# Eload_Aux_Supply_Module_Rev_2.net
KiCad netlist of a schematic drawn in Altium Designer
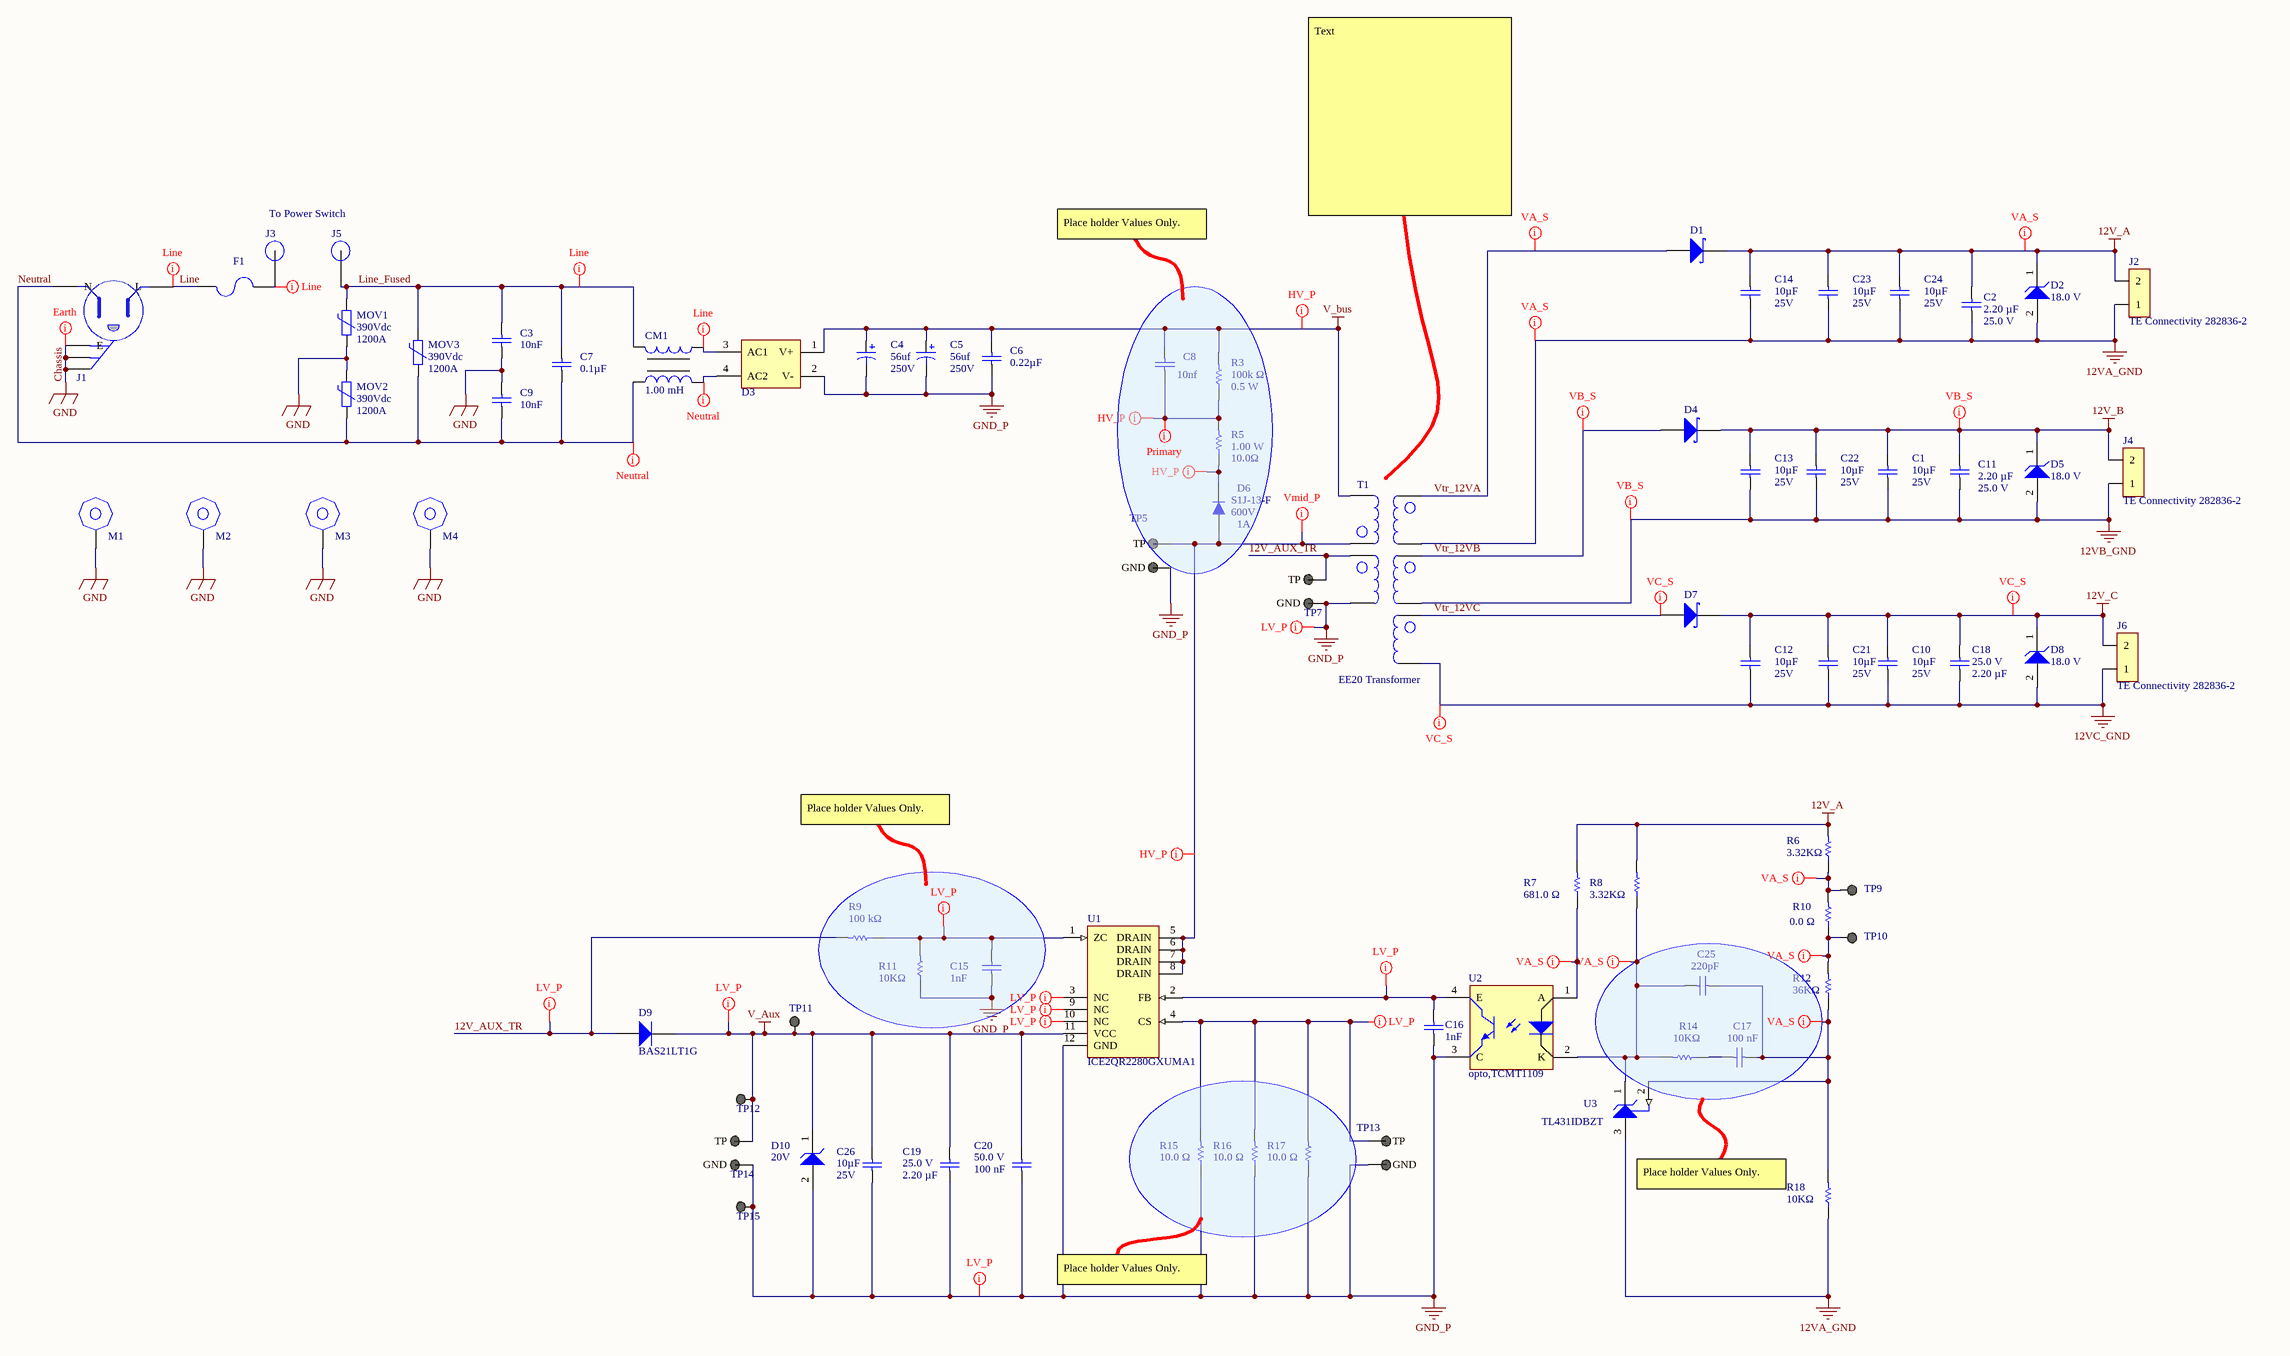
[diagram p0: Eload Aux Supply Module Rev 2.SchDoc]

(export (version "E")
  (design (tool "Eeschema 10.0.6"))
  (components
    (comp (ref "C1")
      (value "Cap")
      (footprint "Cap, 1206")
      (description "10µF ±10% 25V Ceramic Capacitor X7R 1206 (3216 Metric)")
      (fields
        (field (name "MANUFACTURER") "TDK Corporation")
        (field (name "TOLERANCE") "±10%")
        (field (name "CAPACITANCE") "10µF")
        (field (name "VOLTAGE - RATED") "25V")
      )
      (libsource (lib "Master Oct28_2018") (part "CAP,1206,10uF,25V,C3216X7R1E106K160AB"))
    )
    (comp (ref "C2")
      (value "AVX 08053C225KAT2A")
      (footprint "CAP, 0805, HD")
      (description "0805 2.2 uF 25 V ±10 % Tolerance X7R SMT Multilayer Ceramic Capacitor")
      (fields
        (field (name "MANUFACTURER PART NUMBER") "08053C225KAT2A")
        (field (name "VOLTAGE RATING (DC)") "25.0 V")
        (field (name "CAPACITANCE") "2.20 µF")
      )
      (libsource (lib "Master Oct28_2018") (part "Cap,0805,2.2uF,25V,±10%"))
    )
    (comp (ref "C3")
      (value "Cap")
      (footprint "Cap,7.5mm,RFI")
      (description "10000pF ±20% 300VAC Ceramic Capacitor F Radial, Disc")
      (fields
        (field (name "MANUFACTURER") "Murata Electronics North America")
        (field (name "CAPACITANCE") "10nF")
        (field (name "TOLERANCE") "±20%")
      )
      (libsource (lib "Master JUL_2019-Shawn") (part "Cap,RFI,TH,7.5mm,10nF,300Vac,10nF,DE2F3KY103MN3AU02F"))
    )
    (comp (ref "C4")
      (value "Cap,polar,through hole,12.5mm,56uf,250V,20%,UCY2E560MHD1TO")
      (footprint "Cap, Rad, 5mmLead,12.5mmDia,Pin 2+")
      (description "Cap Alum 56uf 20% 250v Radial")
      (fields
        (field (name "MANUFACTURER PART NUMBER") "UCY2E560MHD1TO")
        (field (name "CAP") "56uf")
        (field (name "VOLTAGE RATING") "250V")
      )
      (libsource (lib "Master Oct28_2018") (part "Cap,polar,through hole,12.5mm,56uf,250V,20%,UCY2E560MHD1TO"))
    )
    (comp (ref "C5")
      (value "Cap,polar,through hole,12.5mm,56uf,250V,20%,UCY2E560MHD1TO")
      (footprint "Cap, Rad, 5mmLead,12.5mmDia,Pin 2+")
      (description "Cap Alum 56uf 20% 250v Radial")
      (fields
        (field (name "MANUFACTURER PART NUMBER") "UCY2E560MHD1TO")
        (field (name "CAP") "56uf")
        (field (name "VOLTAGE RATING") "250V")
      )
      (libsource (lib "Master Oct28_2018") (part "Cap,polar,through hole,12.5mm,56uf,250V,20%,UCY2E560MHD1TO"))
    )
    (comp (ref "C6")
      (value "Cap")
      (footprint "Cap, 5mm Lead Spaceing, 4mm dai")
      (description "0.22µF ±10% 250V Ceramic Capacitor X7R Radial")
      (fields
        (field (name "MANUFACTURER") "TDK Corporation")
        (field (name "TOLERANCE") "±10%")
        (field (name "CAPACITANCE") "0.22µF")
      )
      (libsource (lib "Master Oct28_2018") (part "Cap,TH,General Putpose,5mm Spacing, 220nF,250V,FG20X7R2E224KNT06"))
    )
    (comp (ref "C7")
      (value "Cap")
      (footprint "CAP,RFI,15mm Lead Spaceing")
      (description "0.1µF Film Capacitor 305V 630V Polypropylene (PP) Radial")
      (fields
        (field (name "MANUFACTURER") "EPCOS (TDK)")
        (field (name "TOLERANCE") "±20%")
        (field (name "CAPACITANCE") "0.1µF")
      )
      (libsource (lib "Master JUL_2019-Shawn") (part "Cap,RFI,TH,15mm,100nF,305VAC,20%, B32922C3104M000"))
    )
    (comp (ref "C8")
      (value "10nf")
      (footprint "Cap, 5mm Lead Spaceing, 4mm dai")
      (description "10000pF ±5% 630V Ceramic Capacitor C0G, NP0 Radial")
      (fields (field (name "TOLERANCE") "±5%"))
      (libsource (lib "Master Oct28_2018") (part "Cap,,snubber, 10nf,5mm,spacing,630,FG26C0G2J103JNT06"))
    )
    (comp (ref "C9")
      (value "Cap")
      (footprint "Cap,7.5mm,RFI")
      (description "10000pF ±20% 300VAC Ceramic Capacitor F Radial, Disc")
      (fields
        (field (name "MANUFACTURER") "Murata Electronics North America")
        (field (name "CAPACITANCE") "10nF")
        (field (name "TOLERANCE") "±20%")
      )
      (libsource (lib "Master JUL_2019-Shawn") (part "Cap,RFI,TH,7.5mm,10nF,300Vac,10nF,DE2F3KY103MN3AU02F"))
    )
    (comp (ref "C10")
      (value "Cap")
      (footprint "Cap, 1206")
      (description "10µF ±10% 25V Ceramic Capacitor X7R 1206 (3216 Metric)")
      (fields
        (field (name "MANUFACTURER") "TDK Corporation")
        (field (name "TOLERANCE") "±10%")
        (field (name "CAPACITANCE") "10µF")
        (field (name "VOLTAGE - RATED") "25V")
      )
      (libsource (lib "Master Oct28_2018") (part "CAP,1206,10uF,25V,C3216X7R1E106K160AB"))
    )
    (comp (ref "C11")
      (value "AVX 08053C225KAT2A")
      (footprint "CAP, 0805, HD")
      (description "0805 2.2 uF 25 V ±10 % Tolerance X7R SMT Multilayer Ceramic Capacitor")
      (fields
        (field (name "MANUFACTURER PART NUMBER") "08053C225KAT2A")
        (field (name "VOLTAGE RATING (DC)") "25.0 V")
        (field (name "CAPACITANCE") "2.20 µF")
      )
      (libsource (lib "Master Oct28_2018") (part "Cap,0805,2.2uF,25V,±10%"))
    )
    (comp (ref "C12")
      (value "Cap")
      (footprint "Cap, 1206")
      (description "10µF ±10% 25V Ceramic Capacitor X7R 1206 (3216 Metric)")
      (fields
        (field (name "MANUFACTURER") "TDK Corporation")
        (field (name "TOLERANCE") "±10%")
        (field (name "CAPACITANCE") "10µF")
        (field (name "VOLTAGE - RATED") "25V")
      )
      (libsource (lib "Master Oct28_2018") (part "CAP,1206,10uF,25V,C3216X7R1E106K160AB"))
    )
    (comp (ref "C13")
      (value "Cap")
      (footprint "Cap, 1206")
      (description "10µF ±10% 25V Ceramic Capacitor X7R 1206 (3216 Metric)")
      (fields
        (field (name "MANUFACTURER") "TDK Corporation")
        (field (name "TOLERANCE") "±10%")
        (field (name "CAPACITANCE") "10µF")
        (field (name "VOLTAGE - RATED") "25V")
      )
      (libsource (lib "Master Oct28_2018") (part "CAP,1206,10uF,25V,C3216X7R1E106K160AB"))
    )
    (comp (ref "C14")
      (value "Cap")
      (footprint "Cap, 1206")
      (description "10µF ±10% 25V Ceramic Capacitor X7R 1206 (3216 Metric)")
      (fields
        (field (name "MANUFACTURER") "TDK Corporation")
        (field (name "TOLERANCE") "±10%")
        (field (name "CAPACITANCE") "10µF")
        (field (name "VOLTAGE - RATED") "25V")
      )
      (libsource (lib "Master Oct28_2018") (part "CAP,1206,10uF,25V,C3216X7R1E106K160AB"))
    )
    (comp (ref "C15")
      (value "Kemet C0805X102J1GACAUTO")
      (footprint "CAP, 0805, HD")
      (description "CAPACITOR, 1NF, 100V, NP0, 0805")
      (fields (field (name "CAPACITANCE") "1nF"))
      (libsource (lib "Master Oct28_2018") (part "Cap,0805n,1nF,±5%,100Vdc"))
    )
    (comp (ref "C16")
      (value "Kemet C0805X102J1GACAUTO")
      (footprint "CAP, 0805, HD")
      (description "CAPACITOR, 1NF, 100V, NP0, 0805")
      (fields (field (name "CAPACITANCE") "1nF"))
      (libsource (lib "Master Oct28_2018") (part "Cap,0805,1nF,±5%,100Vdc"))
    )
    (comp (ref "C17")
      (value "08055C104JAT2A")
      (footprint "CAP, 0805, HD")
      (description "Capacitor; Ceramic; Cap 0.1 uF; Tol 5%; Vol-Rtg 50 VDC; SMT; 0805; X7R; Tape & Reel")
      (fields (field (name "CAPACITANCE") "100 nF"))
      (libsource (lib "Master Oct28_2018") (part "Cap,0805,100nf,50V,5%,08055C104JAT2A"))
    )
    (comp (ref "C18")
      (value "AVX 08053C225KAT2A")
      (footprint "CAP, 0805, HD")
      (description "0805 2.2 uF 25 V ±10 % Tolerance X7R SMT Multilayer Ceramic Capacitor")
      (fields
        (field (name "MANUFACTURER PART NUMBER") "08053C225KAT2A")
        (field (name "VOLTAGE RATING (DC)") "25.0 V")
        (field (name "CAPACITANCE") "2.20 µF")
      )
      (libsource (lib "Master Oct28_2018") (part "Cap,0805,2.2uF,25V,±10%"))
    )
    (comp (ref "C19")
      (value "AVX 08053C225KAT2A")
      (footprint "CAP, 0805, HD")
      (description "0805 2.2 uF 25 V ±10 % Tolerance X7R SMT Multilayer Ceramic Capacitor")
      (fields
        (field (name "MANUFACTURER PART NUMBER") "08053C225KAT2A")
        (field (name "VOLTAGE RATING (DC)") "25.0 V")
        (field (name "CAPACITANCE") "2.20 µF")
      )
      (libsource (lib "Master Oct28_2018") (part "Cap,0805,2.2uF,25V,±10%"))
    )
    (comp (ref "C20")
      (value "08055C104JAT2A")
      (footprint "CAP, 0805, HD")
      (description "Capacitor; Ceramic; Cap 0.1 uF; Tol 5%; Vol-Rtg 50 VDC; SMT; 0805; X7R; Tape & Reel")
      (fields (field (name "VOLTAGE RATING (DC)") "50.0 V") (field (name "CAPACITANCE") "100 nF"))
      (libsource (lib "Master Oct28_2018") (part "Cap,0805,100nf,50V,5%,08055C104JAT2A"))
    )
    (comp (ref "C21")
      (value "Cap")
      (footprint "Cap, 1206")
      (description "10µF ±10% 25V Ceramic Capacitor X7R 1206 (3216 Metric)")
      (fields
        (field (name "MANUFACTURER") "TDK Corporation")
        (field (name "TOLERANCE") "±10%")
        (field (name "CAPACITANCE") "10µF")
        (field (name "VOLTAGE - RATED") "25V")
      )
      (libsource (lib "Master Oct28_2018") (part "CAP,1206,10uF,25V,C3216X7R1E106K160AB"))
    )
    (comp (ref "C22")
      (value "Cap")
      (footprint "Cap, 1206")
      (description "10µF ±10% 25V Ceramic Capacitor X7R 1206 (3216 Metric)")
      (fields
        (field (name "MANUFACTURER") "TDK Corporation")
        (field (name "TOLERANCE") "±10%")
        (field (name "CAPACITANCE") "10µF")
        (field (name "VOLTAGE - RATED") "25V")
      )
      (libsource (lib "Master Oct28_2018") (part "CAP,1206,10uF,25V,C3216X7R1E106K160AB"))
    )
    (comp (ref "C23")
      (value "Cap")
      (footprint "Cap, 1206")
      (description "10µF ±10% 25V Ceramic Capacitor X7R 1206 (3216 Metric)")
      (fields
        (field (name "MANUFACTURER") "TDK Corporation")
        (field (name "TOLERANCE") "±10%")
        (field (name "CAPACITANCE") "10µF")
        (field (name "VOLTAGE - RATED") "25V")
      )
      (libsource (lib "Master Oct28_2018") (part "CAP,1206,10uF,25V,C3216X7R1E106K160AB"))
    )
    (comp (ref "C24")
      (value "Cap")
      (footprint "Cap, 1206")
      (description "10µF ±10% 25V Ceramic Capacitor X7R 1206 (3216 Metric)")
      (fields
        (field (name "MANUFACTURER") "TDK Corporation")
        (field (name "TOLERANCE") "±10%")
        (field (name "CAPACITANCE") "10µF")
        (field (name "VOLTAGE - RATED") "25V")
      )
      (libsource (lib "Master Oct28_2018") (part "CAP,1206,10uF,25V,C3216X7R1E106K160AB"))
    )
    (comp (ref "C25")
      (value "CC0805KRX7R9BB221")
      (footprint "CAP, 0805, HD")
      (description "220pF ±10% 50V Ceramic Capacitor X7R 0805 (2012 Metric)")
      (fields (field (name "MANUFACTURER") "Yageo") (field (name "CAPACITANCE") "220pF"))
      (libsource (lib "Master Oct28_2018") (part "Cap,0805,220pf,50V,5%,CC0805KRX7R9BB221"))
    )
    (comp (ref "C26")
      (value "Cap")
      (footprint "Cap, 1206")
      (description "10µF ±10% 25V Ceramic Capacitor X7R 1206 (3216 Metric)")
      (fields
        (field (name "MANUFACTURER") "TDK Corporation")
        (field (name "TOLERANCE") "±10%")
        (field (name "CAPACITANCE") "10µF")
        (field (name "VOLTAGE - RATED") "25V")
      )
      (libsource (lib "Master Oct28_2018") (part "CAP,1206,10uF,25V,C3216X7R1E106K160AB"))
    )
    (comp (ref "CM1")
      (value "KEMET SC-03-10G")
      (footprint "Common mode inductor,TLF9UA102W0R8K1")
      (description "CMC 1MH 800MA 2LN TH")
      (fields (field (name "MANUFACTURER PART NUMBER") "SC-03-10G") (field (name "INDUCTANCE") "1.00 mH"))
      (libsource (lib "Master JUL_2019-Shawn") (part "common mode, 1mH,800mA,TLF9UA102W0R8K1"))
    )
    (comp (ref "D1")
      (value "NRVTSA4100ET3G")
      (footprint "DO-214AC, SMA")
      (description "Trench Schottky Rectifier, Very Low Leakage, 100V, 4A")
      (fields (field (name "MANUFACTURER") "ON Semiconductor"))
      (libsource (lib "Master Oct28_2018") (part "Dio,Schottky,4A,400V,NRVTSA4100ET3G"))
    )
    (comp (ref "D2")
      (value "MMSZ4705T1G")
      (footprint "SOD123")
      (description "Zener Diode 18V 500mW ±5% Surface Mount SOD-123")
      (fields (field (name "MANUFACTURER") "ON Semiconductor") (field (name "VOLTAGE RATING (DC)") "18.0 V"))
      (libsource (lib "Master Oct28_2018") (part "diode,Zener, 18V,500mW, SOD123,MMSZ4705T1G"))
    )
    (comp (ref "D3")
      (value "Diode,Bridge, micro-dip,1A,600V, MDB6S")
      (footprint "Micro-DIP, 4-Leads")
      (libsource (lib "Master Mar2024") (part "Diode,Bridge, micro-dip,1A,600V, MDB6S"))
    )
    (comp (ref "D4")
      (value "NRVTSA4100ET3G")
      (footprint "DO-214AC, SMA")
      (description "Trench Schottky Rectifier, Very Low Leakage, 100V, 4A")
      (fields (field (name "MANUFACTURER") "ON Semiconductor"))
      (libsource (lib "Master Oct28_2018") (part "Dio,Schottky,4A,400V,NRVTSA4100ET3G"))
    )
    (comp (ref "D5")
      (value "MMSZ4705T1G")
      (footprint "SOD123")
      (description "Zener Diode 18V 500mW ±5% Surface Mount SOD-123")
      (fields (field (name "MANUFACTURER") "ON Semiconductor") (field (name "VOLTAGE RATING (DC)") "18.0 V"))
      (libsource (lib "Master Oct28_2018") (part "diode,Zener, 18V,500mW, SOD123,MMSZ4705T1G"))
    )
    (comp (ref "D6")
      (value "Diodes Inc. S1J-13-F")
      (footprint "DO-214AC, SMA")
      (description "S1J Series 600 V 1 A Surface Mount Glass Passivated Rectifier - DO-214AC")
      (fields
        (field (name "MANUFACTURER PART NUMBER") "S1J-13-F")
        (field (name "VOLTAGE - DC REVERSE (VR) (MAX)") "600V")
        (field (name "CURRENT") "1A")
      )
      (libsource (lib "Master Oct28_2018") (part "Dio, 1A,600V,S1J-13-F"))
    )
    (comp (ref "D7")
      (value "NRVTSA4100ET3G")
      (footprint "DO-214AC, SMA")
      (description "Trench Schottky Rectifier, Very Low Leakage, 100V, 4A")
      (fields (field (name "MANUFACTURER") "ON Semiconductor"))
      (libsource (lib "Master Oct28_2018") (part "Dio,Schottky,4A,400V,NRVTSA4100ET3G"))
    )
    (comp (ref "D8")
      (value "MMSZ4705T1G")
      (footprint "SOD123")
      (description "Zener Diode 18V 500mW ±5% Surface Mount SOD-123")
      (fields (field (name "MANUFACTURER") "ON Semiconductor") (field (name "VOLTAGE RATING (DC)") "18.0 V"))
      (libsource (lib "Master Oct28_2018") (part "diode,Zener, 18V,500mW, SOD123,MMSZ4705T1G"))
    )
    (comp (ref "D9")
      (value "BAS21LT1G")
      (footprint "SOT23-3")
      (description "Diode Standard 250V 200mA (DC) Surface Mount SOT-23-3 (TO-236)")
      (fields (field (name "MANUFACTURER") "ON Semiconductor") (field (name "BASE PART NUMBER") "BAS21L"))
      (libsource (lib "Master Mar2024") (part "Diode, SOT23,200mA,250V,BAS21LT1G"))
    )
    (comp (ref "D10")
      (value "MMSZ5250BT1G")
      (footprint "SOD123")
      (description "DIODE ZENER 20V 500MW SOD123")
      (fields (field (name "VOLTAGE - ZENER (NOM) (VZ)") "20V") (field (name "TOLERANCE") "±5%"))
      (libsource (lib "Master Oct28_2018") (part "Diode,zener,SOD-123,20V,500mW,MMSZ5250BT1G"))
    )
    (comp (ref "F1")
      (value "Littelfuse 0461.500ER")
      (footprint "Fuse chip, SMD,9.4mm")
      (description "Fuse Chip Slow Blow Acting 0.5A 600V SMD Solder Pad 10.1 X 3.12 X 3.12mm Ceramic T/R")
      (fields (field (name "MANUFACTURER PART NUMBER") "0461.500ER"))
      (libsource (lib "Master Oct28_2018") (part "Fuse,500mA,600V,SMD,0461.500ER"))
    )
    (comp (ref "J1")
      (value "Qualtek 703W-00/54")
      (footprint "conn, IEC320,703W-00/54")
      (description "Inlet, Power; PCB Mount; 250 VAC; 12-15A; Nylon; Black")
      (fields (field (name "MANUFACTURER") "Qualtek"))
      (libsource (lib "Master Oct28_2018") (part "Conn,RCPT,IEC320-C14,703W-00/54"))
    )
    (comp (ref "J2")
      (value "TE Connectivity 282836-2")
      (footprint "TERM BLOCK 2POS SIDE ENTRY 5MM")
      (description "Wire to Board 2 Position 5 mm Pitch 30-16 AWG Euro Style Terminal Block")
      (fields (field (name "MANUFACTURER PART NUMBER") "282836-2"))
      (libsource (lib "Master Oct28_2018") (part "TERM BLOCK 2POS SIDE ENTRY 5MM, 282836-2"))
    )
    (comp (ref "J3")
      (value "Wire Terminal,Quick connect, through hole, Keystone 1287-ST")
      (footprint "Quick connect terminal")
      (description "Brass Tin Plate Vertical .250 inch Tab Sturdi-Mount Male Quick-Fit Terminal")
      (libsource (lib "Master SEPT2019") (part "Wire Terminal,Quick connect, through hole, Keystone 1287-ST"))
    )
    (comp (ref "J4")
      (value "TE Connectivity 282836-2")
      (footprint "TERM BLOCK 2POS SIDE ENTRY 5MM")
      (description "Wire to Board 2 Position 5 mm Pitch 30-16 AWG Euro Style Terminal Block")
      (fields (field (name "MANUFACTURER PART NUMBER") "282836-2"))
      (libsource (lib "Master Oct28_2018") (part "TERM BLOCK 2POS SIDE ENTRY 5MM, 282836-2"))
    )
    (comp (ref "J5")
      (value "Wire Terminal,Quick connect, through hole, Keystone 1287-ST")
      (footprint "Quick connect terminal")
      (description "Brass Tin Plate Vertical .250 inch Tab Sturdi-Mount Male Quick-Fit Terminal")
      (libsource (lib "Master SEPT2019") (part "Wire Terminal,Quick connect, through hole, Keystone 1287-ST"))
    )
    (comp (ref "J6")
      (value "TE Connectivity 282836-2")
      (footprint "TERM BLOCK 2POS SIDE ENTRY 5MM")
      (description "Wire to Board 2 Position 5 mm Pitch 30-16 AWG Euro Style Terminal Block")
      (fields (field (name "MANUFACTURER PART NUMBER") "282836-2"))
      (libsource (lib "Master Oct28_2018") (part "TERM BLOCK 2POS SIDE ENTRY 5MM, 282836-2"))
    )
    (comp (ref "M1")
      (value "M3 hex Standoff")
      (footprint "Standoff,Hex,M3,8mm")
      (description "HEX STANDOFF M3,generic")
      (libsource (lib "Master Oct28_2018") (part "Standoff, M3, Hex"))
    )
    (comp (ref "M2")
      (value "M3 hex Standoff")
      (footprint "Standoff,Hex,M3,8mm")
      (description "HEX STANDOFF M3,generic")
      (libsource (lib "Master Oct28_2018") (part "Standoff, M3, Hex"))
    )
    (comp (ref "M3")
      (value "M3 hex Standoff")
      (footprint "Standoff,Hex,M3,8mm")
      (description "HEX STANDOFF M3,generic")
      (libsource (lib "Master Oct28_2018") (part "Standoff, M3, Hex"))
    )
    (comp (ref "M4")
      (value "M3 hex Standoff")
      (footprint "Standoff,Hex,M3,8mm")
      (description "HEX STANDOFF M3,generic")
      (libsource (lib "Master Oct28_2018") (part "Standoff, M3, Hex"))
    )
    (comp (ref "MOV1")
      (value "MOV, though hole, 390V, 1.2kA, B72207S0251K101")
      (footprint "MOV, 5mm spacing")
      (description "390V 1.2kA Varistor 1 Circuit Through Hole Disc 7mm")
      (fields (field (name "DC CLAMPING VOLTAGE") "390Vdc") (field (name "CLAMPING CURRENT") "1200A"))
      (libsource (lib "Master Oct28_2018") (part "MOV, though hole, 390V, 1.2kA, B72207S0251K101"))
    )
    (comp (ref "MOV2")
      (value "MOV, though hole, 390V, 1.2kA, B72207S0251K101")
      (footprint "MOV, 5mm spacing")
      (description "390V 1.2kA Varistor 1 Circuit Through Hole Disc 7mm")
      (fields (field (name "DC CLAMPING VOLTAGE") "390Vdc") (field (name "CLAMPING CURRENT") "1200A"))
      (libsource (lib "Master Oct28_2018") (part "MOV, though hole, 390V, 1.2kA, B72207S0251K101"))
    )
    (comp (ref "MOV3")
      (value "MOV, though hole, 390V, 1.2kA, B72207S0251K101")
      (footprint "MOV, 5mm spacing")
      (description "390V 1.2kA Varistor 1 Circuit Through Hole Disc 7mm")
      (fields (field (name "DC CLAMPING VOLTAGE") "390Vdc") (field (name "CLAMPING CURRENT") "1200A"))
      (libsource (lib "Master Oct28_2018") (part "MOV, though hole, 390V, 1.2kA, B72207S0251K101"))
    )
    (comp (ref "R3")
      (value "Panasonic ERJ-14NF1003U")
      (footprint "Res,1210")
      (description "Thick Film Resistors - SMD 1210 100Kohms 1% Tol")
      (fields (field (name "POWER RATING") "0.5 W") (field (name "RESISTANCE") "100k Ω"))
      (libsource (lib "Master Oct28_2018") (part "Res,1210,100K,1%,0.5W,200V"))
    )
    (comp (ref "R5")
      (value "Bourns CRS2010-JX-100ELF")
      (footprint "Resistor,2010,1W")
      (description "Surface Mount Chip Resistor, Thick Film, CRS Series, 10 ohm, 1 W, 5%, 400 V, 2010 [5025 Metric]")
      (fields
        (field (name "MANUFACTURER PART NUMBER") "CRS2010-JX-100ELF")
        (field (name "POWER RATING") "1.00 W")
        (field (name "RESISTANCE") "10.0Ω")
      )
      (libsource (lib "Master Oct28_2018") (part "Res,2010,10.0Ω,±5%,1W,400V"))
    )
    (comp (ref "R6")
      (value "Vishay Dale CRCW08053K32FKEA")
      (footprint "res, 0805, HD")
      (description "RES SMD 3.32K OHM 1% 1/8W 0805")
      (fields (field (name "RESISTANCE") "3.32KΩ"))
      (libsource (lib "Master Oct28_2018") (part "Res,0805,3.32K,±1%,100.0 ppm/°C,150.0 V,CRCW08053K32FKEA"))
    )
    (comp (ref "R7")
      (value "Vishay Dale CRCW0805681RFKEA")
      (footprint "res, 0805, HD")
      (description "RES SMD 681 OHM 1% 1/8W 0805")
      (fields (field (name "RESISTANCE") "681.0 Ω"))
      (libsource (lib "Master Oct28_2018") (part "Res,0805,681.0 Ω,±1%,100.0 ppm/°C,150.0 V,CRCW0805681RFKEA"))
    )
    (comp (ref "R8")
      (value "Vishay Dale CRCW08053K32FKEA")
      (footprint "res, 0805, HD")
      (description "RES SMD 3.32K OHM 1% 1/8W 0805")
      (fields (field (name "RESISTANCE") "3.32KΩ"))
      (libsource (lib "Master Oct28_2018") (part "Res,0805,3.32K,±1%,100.0 ppm/°C,150.0 V,CRCW08053K32FKEA"))
    )
    (comp (ref "R9")
      (value "Res,0805,100kΩ,1%,100ppm,CRCW0805100KFKEA")
      (footprint "res, 0805, HD")
      (description "100 kOhms ±1% 0.125W, 1/8W Chip Resistor 0805 (2012 Metric) Thick Film")
      (fields
        (field (name "MANUFACTURER PART NUMBER") "CRCW0805100KFKEA")
        (field (name "MANUFACTURER") "Vishay")
        (field (name "RESISTANCE") "100 kΩ")
      )
      (libsource (lib "Master Oct28_2018") (part "Res,0805,100kΩ,1%,100ppm,CRCW0805100KFKEA"))
    )
    (comp (ref "R10")
      (value "Vishay Dale CRCW08050000Z0EAHP")
      (footprint "res, 0805, HD")
      (description "RES SMD 0.0 OHM JUMPER 1/3W 0805")
      (fields (field (name "RESISTANCE") "0.0 Ω"))
      (libsource (lib "Master Oct28_2018") (part "Res,0805,0.0Ω,150V"))
    )
    (comp (ref "R11")
      (value "Vishay / Dale CRCW080510K0FKTA")
      (footprint "res, 0805, HD")
      (description "RES SMD 10K OHM 1% 1/8W 0805")
      (fields (field (name "RESISTANCE") "10KΩ"))
      (libsource (lib "Master Oct28_2018") (part "Res,0805,10.0kΩ,1%,100 ppm,CRCW080510K0FKTA"))
    )
    (comp (ref "R12")
      (value "Vishay Dale CRCW080536K0FKEA")
      (footprint "res, 0805, HD")
      (description "RES SMD 36K OHM 1% 1/8W 0805")
      (fields
        (field (name "MANUFACTURER") "Vishay")
        (field (name "TOLERANCE") "1 %")
        (field (name "RESISTANCE") "36KΩ")
      )
      (libsource (lib "Master Oct28_2018") (part "Res,0805,36KΩ,1 %,100ppm,150 V,CRCW080536K0FKEA"))
    )
    (comp (ref "R14")
      (value "Vishay / Dale CRCW080510K0FKTA")
      (footprint "res, 0805, HD")
      (description "RES SMD 10K OHM 1% 1/8W 0805")
      (fields (field (name "RESISTANCE") "10KΩ"))
      (libsource (lib "Master Oct28_2018") (part "Res,0805,10.0kΩ,1%,100 ppm,CRCW080510K0FKTA"))
    )
    (comp (ref "R15")
      (value "RP73D2B10RBTG")
      (footprint "Res,1210")
      (description "Surface Mount Thin Film Resistor, RP73 Series, 10 ohm, 250 mW, - 0.1%, 200 V")
      (fields (field (name "RESISTANCE") "10.0 Ω"))
      (libsource (lib "Master Oct28_2018") (part "Res,1210,10.0 Ω,±0.1%,200V,RP73D2B10RBTG"))
    )
    (comp (ref "R16")
      (value "RP73D2B10RBTG")
      (footprint "Res,1210")
      (description "Surface Mount Thin Film Resistor, RP73 Series, 10 ohm, 250 mW, - 0.1%, 200 V")
      (fields (field (name "RESISTANCE") "10.0 Ω"))
      (libsource (lib "Master Oct28_2018") (part "Res,1210,10.0 Ω,±0.1%,200V,RP73D2B10RBTG"))
    )
    (comp (ref "R17")
      (value "RP73D2B10RBTG")
      (footprint "Res,1210")
      (description "Surface Mount Thin Film Resistor, RP73 Series, 10 ohm, 250 mW, - 0.1%, 200 V")
      (fields (field (name "RESISTANCE") "10.0 Ω"))
      (libsource (lib "Master Oct28_2018") (part "Res,1210,10.0 Ω,±0.1%,200V,RP73D2B10RBTG"))
    )
    (comp (ref "R18")
      (value "Vishay / Dale CRCW080510K0FKTA")
      (footprint "res, 0805, HD")
      (description "RES SMD 10K OHM 1% 1/8W 0805")
      (fields (field (name "RESISTANCE") "10KΩ"))
      (libsource (lib "Master Oct28_2018") (part "Res,0805,10.0kΩ,1%,100 ppm,CRCW080510K0FKTA"))
    )
    (comp (ref "T1")
      (value "EE20 Transformer")
      (footprint "Transformer EE20, 10 Pos")
      (description "EE20 Transformer Assembly")
      (libsource (lib "Master Oct28_2018") (part "Transformer E20-10-6 Vertical"))
    )
    (comp (ref "TP5")
      (value "Scope Probe TP")
      (footprint "ScopeProbe_TP-Tektronix")
      (description "Tektronix Scope Probe Short Lead Test Point")
      (libsource (lib "Master Oct28_2018") (part "Test Point, Tektronix Scope Probe Short Lead Test Point"))
    )
    (comp (ref "TP7")
      (value "Scope Probe TP")
      (footprint "ScopeProbe_TP-Tektronix")
      (description "Tektronix Scope Probe Short Lead Test Point")
      (libsource (lib "Master Oct28_2018") (part "Test Point, Tektronix Scope Probe Short Lead Test Point"))
    )
    (comp (ref "TP9")
      (value "Keystone 5014")
      (footprint "Test Point, Keystone 5014")
      (description "Test Point; Yellow; Thru-Hole; Snap-Fit; SilverPlate; 0.063in. Dia.; 0.445In.")
      (fields (field (name "MANUFACTURER PART NUMBER") "5014"))
      (libsource (lib "Master Oct28_2018") (part "Test Point; Yellow; Thru-Hole; Snap-Fit,Keystone   5014"))
    )
    (comp (ref "TP10")
      (value "Keystone 5014")
      (footprint "Test Point, Keystone 5014")
      (description "Test Point; Yellow; Thru-Hole; Snap-Fit; SilverPlate; 0.063in. Dia.; 0.445In.")
      (fields (field (name "MANUFACTURER PART NUMBER") "5014"))
      (libsource (lib "Master Oct28_2018") (part "Test Point; Yellow; Thru-Hole; Snap-Fit,Keystone   5014"))
    )
    (comp (ref "TP11")
      (value "Keystone 5014")
      (footprint "Test Point, Keystone 5014")
      (description "Test Point; Yellow; Thru-Hole; Snap-Fit; SilverPlate; 0.063in. Dia.; 0.445In.")
      (fields (field (name "MANUFACTURER PART NUMBER") "5014"))
      (libsource (lib "Master Oct28_2018") (part "Test Point; Yellow; Thru-Hole; Snap-Fit,Keystone   5014"))
    )
    (comp (ref "TP12")
      (value "Keystone 5014")
      (footprint "Test Point, Keystone 5014")
      (description "Test Point; Yellow; Thru-Hole; Snap-Fit; SilverPlate; 0.063in. Dia.; 0.445In.")
      (fields (field (name "MANUFACTURER PART NUMBER") "5014"))
      (libsource (lib "") (part "Test Point; Yellow; Thru-Hole; Snap-Fit,Keystone   5014_1"))
    )
    (comp (ref "TP13")
      (value "Scope Probe TP")
      (footprint "ScopeProbe_TP-Tektronix")
      (description "Tektronix Scope Probe Short Lead Test Point")
      (libsource (lib "Master Oct28_2018") (part "Test Point, Tektronix Scope Probe Short Lead Test Point"))
    )
    (comp (ref "TP14")
      (value "Scope Probe TP")
      (footprint "ScopeProbe_TP-Tektronix")
      (description "Tektronix Scope Probe Short Lead Test Point")
      (libsource (lib "Master Oct28_2018") (part "Test Point, Tektronix Scope Probe Short Lead Test Point"))
    )
    (comp (ref "TP15")
      (value "Keystone 5014")
      (footprint "Test Point, Keystone 5014")
      (description "Test Point; Yellow; Thru-Hole; Snap-Fit; SilverPlate; 0.063in. Dia.; 0.445In.")
      (fields (field (name "MANUFACTURER PART NUMBER") "5014"))
      (libsource (lib "Master Oct28_2018") (part "Test Point; Yellow; Thru-Hole; Snap-Fit,Keystone   5014"))
    )
    (comp (ref "U1")
      (value "Infineon ICE2QR2280GXUMA1")
      (footprint "SOP, 16-Leads")
      (description "Off Line SMPS Quasi-Resonant PWM Controller 12-Pin DSO T/R")
      (fields (field (name "MFG P/N") "ICE2QR2280GXUMA1"))
      (libsource (lib "Master Oct28_2018") (part "controller, flyback, QR, ICE2QR2280GXUMA1"))
    )
    (comp (ref "U2")
      (value "opto,TCMT1109")
      (footprint "SSOP, 4-Leads")
      (description "Optocoupler DC-IN 1-CH Transistor DC-OUT 4-Pin Mini-Flat T/R")
      (libsource (lib "Master Oct28_2018") (part "opto,TCMT1109"))
    )
    (comp (ref "U3")
      (value "Shunt Regulator,2.5Vdc TL431IDBZT")
      (footprint "SOT23-3")
      (fields (field (name "MANUFACTURER PART NUMBER") "TL431IDBZT"))
      (libsource (lib "Master Oct28_2018") (part "Shunt Regulator,2.5Vdc TL431IDBZT"))
    )
  )
  (nets
    (net (code "1") (name "/12V_AUX_TR") (class "Default")
      (node (ref "D9") (pin "1") (pinfunction "A_1") (pintype "passive"))
      (node (ref "R9") (pin "2") (pinfunction "2_2") (pintype "passive"))
      (node (ref "T1") (pin "3") (pinfunction "3_3") (pintype "passive"))
      (node (ref "TP7") (pin "2") (pinfunction "TP_2") (pintype "passive"))
    )
    (net (code "2") (name "/Line") (class "Default")
      (node (ref "F1") (pin "1") (pinfunction "1_1") (pintype "passive"))
      (node (ref "J1") (pin "1") (pinfunction "L_1") (pintype "passive"))
    )
    (net (code "3") (name "/Line_Fused") (class "Default")
      (node (ref "C3") (pin "2") (pinfunction "2_2") (pintype "passive"))
      (node (ref "C7") (pin "2") (pinfunction "2_2") (pintype "passive"))
      (node (ref "CM1") (pin "3") (pinfunction "3_3") (pintype "passive"))
      (node (ref "J5") (pin "1") (pinfunction "1_1") (pintype "passive"))
      (node (ref "MOV1") (pin "2") (pinfunction "2_2") (pintype "passive"))
      (node (ref "MOV3") (pin "2") (pinfunction "2_2") (pintype "passive"))
    )
    (net (code "4") (name "/Neutral") (class "Default")
      (node (ref "C7") (pin "1") (pinfunction "1_1") (pintype "passive"))
      (node (ref "C9") (pin "1") (pinfunction "1_1") (pintype "passive"))
      (node (ref "CM1") (pin "1") (pinfunction "1_1") (pintype "passive"))
      (node (ref "J1") (pin "3") (pinfunction "N_3") (pintype "passive"))
      (node (ref "MOV2") (pin "1") (pinfunction "1_1") (pintype "passive"))
      (node (ref "MOV3") (pin "1") (pinfunction "1_1") (pintype "passive"))
    )
    (net (code "5") (name "/Vtr_12VA") (class "Default")
      (node (ref "D1") (pin "2") (pinfunction "A_2") (pintype "passive"))
      (node (ref "T1") (pin "6") (pinfunction "6_6") (pintype "passive"))
    )
    (net (code "6") (name "/Vtr_12VB") (class "Default")
      (node (ref "D4") (pin "2") (pinfunction "A_2") (pintype "passive"))
      (node (ref "T1") (pin "8") (pinfunction "8_8") (pintype "passive"))
    )
    (net (code "7") (name "/Vtr_12VC") (class "Default")
      (node (ref "D7") (pin "2") (pinfunction "A_2") (pintype "passive"))
      (node (ref "T1") (pin "10") (pinfunction "10_10") (pintype "passive"))
    )
    (net (code "8") (name "12VA_GND") (class "Default")
      (node (ref "C14") (pin "1") (pinfunction "1_1") (pintype "passive"))
      (node (ref "C2") (pin "1") (pinfunction "1_1") (pintype "passive"))
      (node (ref "C23") (pin "1") (pinfunction "1_1") (pintype "passive"))
      (node (ref "C24") (pin "1") (pinfunction "1_1") (pintype "passive"))
      (node (ref "D2") (pin "2") (pinfunction "A_2") (pintype "passive"))
      (node (ref "J2") (pin "1") (pinfunction "1_1") (pintype "passive"))
      (node (ref "R18") (pin "1") (pinfunction "1_1") (pintype "passive"))
      (node (ref "T1") (pin "5") (pinfunction "5_5") (pintype "passive"))
      (node (ref "U3") (pin "3") (pinfunction "ANODE_3") (pintype "passive"))
    )
    (net (code "9") (name "12VB_GND") (class "Default")
      (node (ref "C1") (pin "1") (pinfunction "1_1") (pintype "passive"))
      (node (ref "C11") (pin "1") (pinfunction "1_1") (pintype "passive"))
      (node (ref "C13") (pin "1") (pinfunction "1_1") (pintype "passive"))
      (node (ref "C22") (pin "1") (pinfunction "1_1") (pintype "passive"))
      (node (ref "D5") (pin "2") (pinfunction "A_2") (pintype "passive"))
      (node (ref "J4") (pin "1") (pinfunction "1_1") (pintype "passive"))
      (node (ref "T1") (pin "7") (pinfunction "7_7") (pintype "passive"))
    )
    (net (code "10") (name "12VC_GND") (class "Default")
      (node (ref "C10") (pin "1") (pinfunction "1_1") (pintype "passive"))
      (node (ref "C12") (pin "1") (pinfunction "1_1") (pintype "passive"))
      (node (ref "C18") (pin "1") (pinfunction "1_1") (pintype "passive"))
      (node (ref "C21") (pin "1") (pinfunction "1_1") (pintype "passive"))
      (node (ref "D8") (pin "2") (pinfunction "A_2") (pintype "passive"))
      (node (ref "J6") (pin "1") (pinfunction "1_1") (pintype "passive"))
      (node (ref "T1") (pin "9") (pinfunction "9_9") (pintype "passive"))
    )
    (net (code "11") (name "12V_A") (class "Default")
      (node (ref "C14") (pin "2") (pinfunction "2_2") (pintype "passive"))
      (node (ref "C2") (pin "2") (pinfunction "2_2") (pintype "passive"))
      (node (ref "C23") (pin "2") (pinfunction "2_2") (pintype "passive"))
      (node (ref "C24") (pin "2") (pinfunction "2_2") (pintype "passive"))
      (node (ref "D1") (pin "1") (pinfunction "K_1") (pintype "passive"))
      (node (ref "D2") (pin "1") (pinfunction "K_1") (pintype "passive"))
      (node (ref "J2") (pin "2") (pinfunction "2_2") (pintype "passive"))
      (node (ref "R6") (pin "2") (pinfunction "2_2") (pintype "passive"))
      (node (ref "R7") (pin "2") (pinfunction "2_2") (pintype "passive"))
      (node (ref "R8") (pin "2") (pinfunction "2_2") (pintype "passive"))
    )
    (net (code "12") (name "12V_B") (class "Default")
      (node (ref "C1") (pin "2") (pinfunction "2_2") (pintype "passive"))
      (node (ref "C11") (pin "2") (pinfunction "2_2") (pintype "passive"))
      (node (ref "C13") (pin "2") (pinfunction "2_2") (pintype "passive"))
      (node (ref "C22") (pin "2") (pinfunction "2_2") (pintype "passive"))
      (node (ref "D4") (pin "1") (pinfunction "K_1") (pintype "passive"))
      (node (ref "D5") (pin "1") (pinfunction "K_1") (pintype "passive"))
      (node (ref "J4") (pin "2") (pinfunction "2_2") (pintype "passive"))
    )
    (net (code "13") (name "12V_C") (class "Default")
      (node (ref "C10") (pin "2") (pinfunction "2_2") (pintype "passive"))
      (node (ref "C12") (pin "2") (pinfunction "2_2") (pintype "passive"))
      (node (ref "C18") (pin "2") (pinfunction "2_2") (pintype "passive"))
      (node (ref "C21") (pin "2") (pinfunction "2_2") (pintype "passive"))
      (node (ref "D7") (pin "1") (pinfunction "K_1") (pintype "passive"))
      (node (ref "D8") (pin "1") (pinfunction "K_1") (pintype "passive"))
      (node (ref "J6") (pin "2") (pinfunction "2_2") (pintype "passive"))
    )
    (net (code "14") (name "GND") (class "Default")
      (node (ref "C3") (pin "1") (pinfunction "1_1") (pintype "passive"))
      (node (ref "C9") (pin "2") (pinfunction "2_2") (pintype "passive"))
      (node (ref "J1") (pin "2") (pinfunction "E_2") (pintype "passive"))
      (node (ref "J1") (pin "4") (pinfunction "E_4") (pintype "passive"))
      (node (ref "J1") (pin "5") (pinfunction "E_5") (pintype "passive"))
      (node (ref "M1") (pin "0") (pinfunction "0_0") (pintype "passive"))
      (node (ref "M2") (pin "0") (pinfunction "0_0") (pintype "passive"))
      (node (ref "M3") (pin "0") (pinfunction "0_0") (pintype "passive"))
      (node (ref "M4") (pin "0") (pinfunction "0_0") (pintype "passive"))
      (node (ref "MOV1") (pin "1") (pinfunction "1_1") (pintype "passive"))
      (node (ref "MOV2") (pin "2") (pinfunction "2_2") (pintype "passive"))
    )
    (net (code "15") (name "GND_P") (class "Default")
      (node (ref "C15") (pin "1") (pinfunction "1_1") (pintype "passive"))
      (node (ref "C16") (pin "1") (pinfunction "1_1") (pintype "passive"))
      (node (ref "C19") (pin "1") (pinfunction "1_1") (pintype "passive"))
      (node (ref "C20") (pin "1") (pinfunction "1_1") (pintype "passive"))
      (node (ref "C26") (pin "1") (pinfunction "1_1") (pintype "passive"))
      (node (ref "C4") (pin "1") (pinfunction "1_1") (pintype "passive"))
      (node (ref "C5") (pin "1") (pinfunction "1_1") (pintype "passive"))
      (node (ref "C6") (pin "1") (pinfunction "1_1") (pintype "passive"))
      (node (ref "D10") (pin "2") (pinfunction "A_2") (pintype "passive"))
      (node (ref "D3") (pin "2") (pinfunction "V-_2") (pintype "power_in"))
      (node (ref "R11") (pin "1") (pinfunction "1_1") (pintype "passive"))
      (node (ref "R15") (pin "1") (pinfunction "1_1") (pintype "passive"))
      (node (ref "R16") (pin "1") (pinfunction "1_1") (pintype "passive"))
      (node (ref "R17") (pin "1") (pinfunction "1_1") (pintype "passive"))
      (node (ref "T1") (pin "4") (pinfunction "4_4") (pintype "passive"))
      (node (ref "TP13") (pin "1") (pinfunction "GND_1") (pintype "passive"))
      (node (ref "TP14") (pin "1") (pinfunction "GND_1") (pintype "passive"))
      (node (ref "TP15") (pin "1") (pinfunction "1_1") (pintype "passive"))
      (node (ref "TP5") (pin "1") (pinfunction "GND_1") (pintype "passive"))
      (node (ref "TP7") (pin "1") (pinfunction "GND_1") (pintype "passive"))
      (node (ref "U1") (pin "12") (pinfunction "GND_12") (pintype "power_in"))
      (node (ref "U2") (pin "3") (pinfunction "C_3") (pintype "passive"))
    )
    (net (code "16") (name "Net-(C8-Pad1)") (class "Default")
      (node (ref "C8") (pin "1") (pinfunction "1_1") (pintype "passive"))
      (node (ref "R3") (pin "1") (pinfunction "1_1") (pintype "passive"))
      (node (ref "R5") (pin "2") (pinfunction "2_2") (pintype "passive"))
    )
    (net (code "17") (name "Net-(C17-Pad2)") (class "Default")
      (node (ref "C17") (pin "2") (pinfunction "2_2") (pintype "passive"))
      (node (ref "R14") (pin "1") (pinfunction "1_1") (pintype "passive"))
    )
    (net (code "18") (name "Net-(D3-AC1)") (class "Default")
      (node (ref "CM1") (pin "2") (pinfunction "2_2") (pintype "passive"))
      (node (ref "D3") (pin "3") (pinfunction "AC1_3") (pintype "power_in"))
    )
    (net (code "19") (name "Net-(D3-AC2)") (class "Default")
      (node (ref "CM1") (pin "4") (pinfunction "4_4") (pintype "passive"))
      (node (ref "D3") (pin "4") (pinfunction "AC2_4") (pintype "power_in"))
    )
    (net (code "20") (name "Net-(D6-A)") (class "Default")
      (node (ref "D6") (pin "1") (pinfunction "A_1") (pintype "passive"))
      (node (ref "T1") (pin "2") (pinfunction "2_2") (pintype "passive"))
      (node (ref "TP5") (pin "2") (pinfunction "TP_2") (pintype "passive"))
      (node (ref "U1") (pin "5") (pinfunction "DRAIN_5") (pintype "power_in"))
      (node (ref "U1") (pin "6") (pinfunction "DRAIN_6") (pintype "power_in"))
      (node (ref "U1") (pin "7") (pinfunction "DRAIN_7") (pintype "power_in"))
      (node (ref "U1") (pin "8") (pinfunction "DRAIN_8") (pintype "power_in"))
    )
    (net (code "21") (name "Net-(D6-K)") (class "Default")
      (node (ref "D6") (pin "2") (pinfunction "K_2") (pintype "passive"))
      (node (ref "R5") (pin "1") (pinfunction "1_1") (pintype "passive"))
    )
    (net (code "22") (name "Net-(F1-Pad2)") (class "Default")
      (node (ref "F1") (pin "2") (pinfunction "2_2") (pintype "passive"))
      (node (ref "J3") (pin "1") (pinfunction "1_1") (pintype "passive"))
    )
    (net (code "23") (name "Net-(R10-Pad1)") (class "Default")
      (node (ref "R10") (pin "1") (pinfunction "1_1") (pintype "passive"))
      (node (ref "R12") (pin "2") (pinfunction "2_2") (pintype "passive"))
      (node (ref "TP10") (pin "1") (pinfunction "1_1") (pintype "passive"))
    )
    (net (code "24") (name "Net-(R10-Pad2)") (class "Default")
      (node (ref "R10") (pin "2") (pinfunction "2_2") (pintype "passive"))
      (node (ref "R6") (pin "1") (pinfunction "1_1") (pintype "passive"))
      (node (ref "TP9") (pin "1") (pinfunction "1_1") (pintype "passive"))
    )
    (net (code "25") (name "Net-(TP13-TP)") (class "Default")
      (node (ref "R15") (pin "2") (pinfunction "2_2") (pintype "passive"))
      (node (ref "R16") (pin "2") (pinfunction "2_2") (pintype "passive"))
      (node (ref "R17") (pin "2") (pinfunction "2_2") (pintype "passive"))
      (node (ref "TP13") (pin "2") (pinfunction "TP_2") (pintype "passive"))
      (node (ref "U1") (pin "4") (pinfunction "CS_4") (pintype "input"))
    )
    (net (code "26") (name "Net-(U1-FB)") (class "Default")
      (node (ref "C16") (pin "2") (pinfunction "2_2") (pintype "passive"))
      (node (ref "U1") (pin "2") (pinfunction "FB_2") (pintype "input"))
      (node (ref "U2") (pin "4") (pinfunction "E_4") (pintype "passive"))
    )
    (net (code "27") (name "Net-(U1-ZC)") (class "Default")
      (node (ref "C15") (pin "2") (pinfunction "2_2") (pintype "passive"))
      (node (ref "R11") (pin "2") (pinfunction "2_2") (pintype "passive"))
      (node (ref "R9") (pin "1") (pinfunction "1_1") (pintype "passive"))
      (node (ref "U1") (pin "1") (pinfunction "ZC_1") (pintype "input"))
    )
    (net (code "28") (name "Net-(U2-A)") (class "Default")
      (node (ref "R7") (pin "1") (pinfunction "1_1") (pintype "passive"))
      (node (ref "U2") (pin "1") (pinfunction "A_1") (pintype "passive"))
    )
    (net (code "29") (name "Net-(U2-K)") (class "Default")
      (node (ref "C25") (pin "1") (pinfunction "1_1") (pintype "passive"))
      (node (ref "R14") (pin "2") (pinfunction "2_2") (pintype "passive"))
      (node (ref "R8") (pin "1") (pinfunction "1_1") (pintype "passive"))
      (node (ref "U2") (pin "2") (pinfunction "K_2") (pintype "passive"))
      (node (ref "U3") (pin "1") (pinfunction "CATHODE_1") (pintype "passive"))
    )
    (net (code "30") (name "Net-(U3-REF)") (class "Default")
      (node (ref "C17") (pin "1") (pinfunction "1_1") (pintype "passive"))
      (node (ref "C25") (pin "2") (pinfunction "2_2") (pintype "passive"))
      (node (ref "R12") (pin "1") (pinfunction "1_1") (pintype "passive"))
      (node (ref "R18") (pin "2") (pinfunction "2_2") (pintype "passive"))
      (node (ref "U3") (pin "2") (pinfunction "REF_2") (pintype "input"))
    )
    (net (code "31") (name "V_Aux") (class "Default")
      (node (ref "C19") (pin "2") (pinfunction "2_2") (pintype "passive"))
      (node (ref "C20") (pin "2") (pinfunction "2_2") (pintype "passive"))
      (node (ref "C26") (pin "2") (pinfunction "2_2") (pintype "passive"))
      (node (ref "D10") (pin "1") (pinfunction "K_1") (pintype "passive"))
      (node (ref "D9") (pin "3") (pinfunction "K_3") (pintype "passive"))
      (node (ref "TP11") (pin "1") (pinfunction "1_1") (pintype "passive"))
      (node (ref "TP12") (pin "1") (pinfunction "1_1") (pintype "passive"))
      (node (ref "TP14") (pin "2") (pinfunction "TP_2") (pintype "passive"))
      (node (ref "U1") (pin "11") (pinfunction "VCC_11") (pintype "power_in"))
    )
    (net (code "32") (name "V_bus") (class "Default")
      (node (ref "C4") (pin "2") (pinfunction "2_2") (pintype "passive"))
      (node (ref "C5") (pin "2") (pinfunction "2_2") (pintype "passive"))
      (node (ref "C6") (pin "2") (pinfunction "2_2") (pintype "passive"))
      (node (ref "C8") (pin "2") (pinfunction "2_2") (pintype "passive"))
      (node (ref "D3") (pin "1") (pinfunction "V+_1") (pintype "power_in"))
      (node (ref "R3") (pin "2") (pinfunction "2_2") (pintype "passive"))
      (node (ref "T1") (pin "1") (pinfunction "1_1") (pintype "passive"))
    )
    (net (code "33") (name "unconnected-(U1-NC-Pad3)") (class "Default")
      (node (ref "U1") (pin "3") (pinfunction "NC_3") (pintype "passive"))
    )
    (net (code "34") (name "unconnected-(U1-NC-Pad9)") (class "Default")
      (node (ref "U1") (pin "9") (pinfunction "NC_9") (pintype "passive"))
    )
    (net (code "35") (name "unconnected-(U1-NC-Pad10)") (class "Default")
      (node (ref "U1") (pin "10") (pinfunction "NC_10") (pintype "passive"))
    )
  )
)
